# CANBUS_3V3_Isolated.net
KiCad netlist of a schematic drawn in Altium Designer
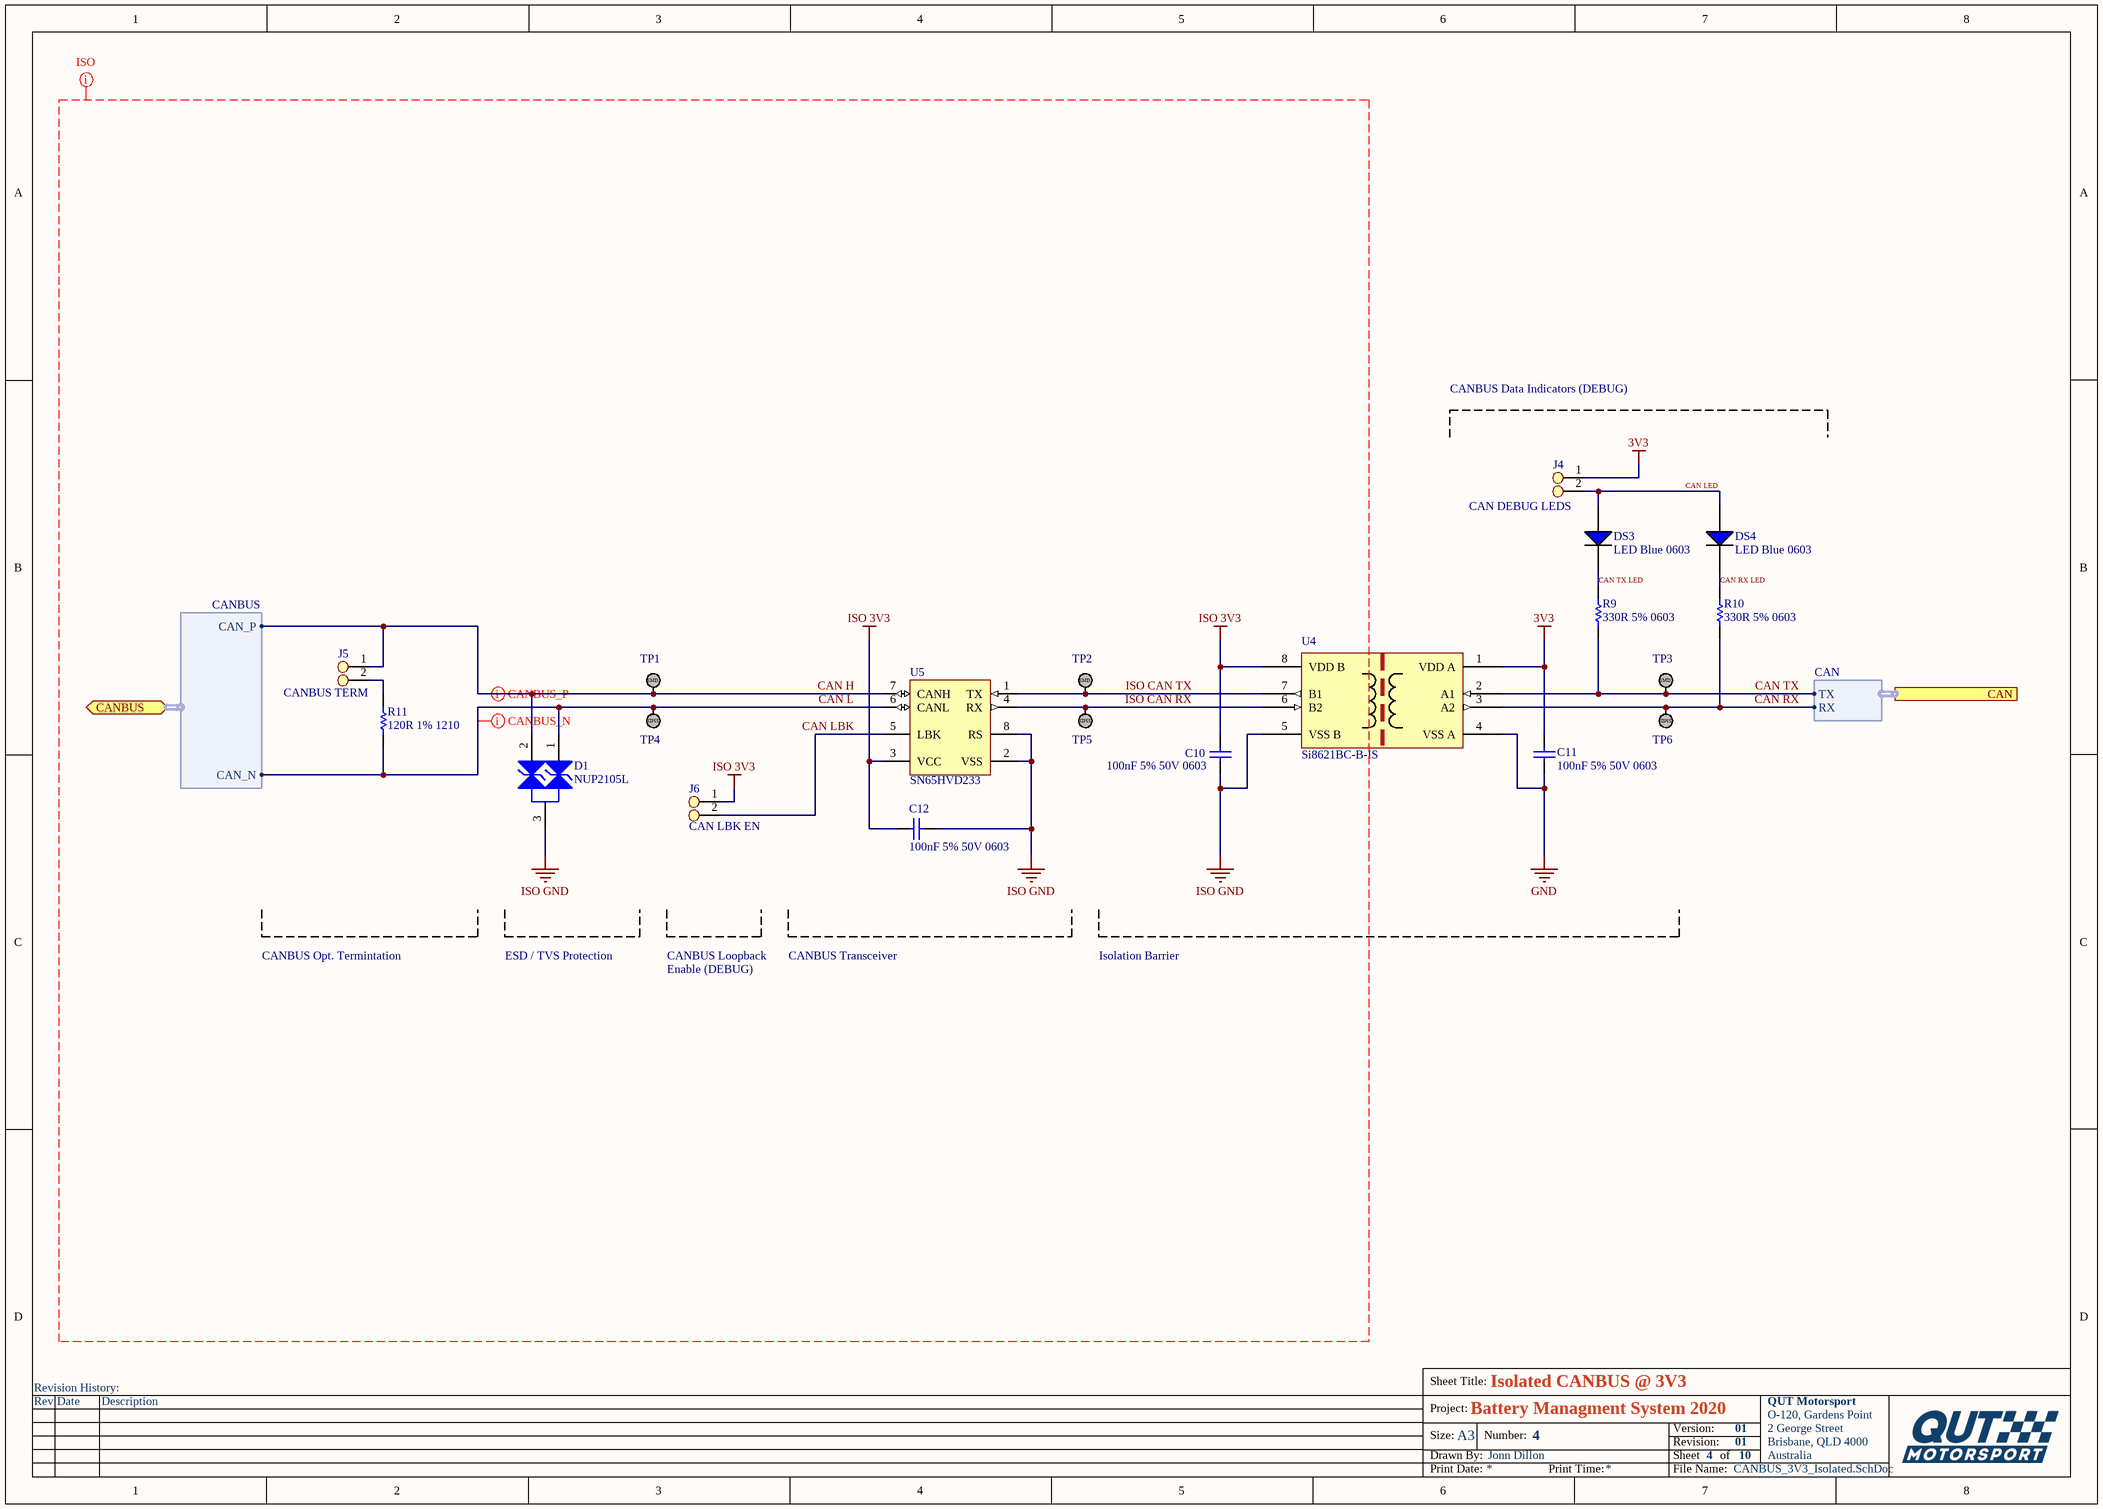
[diagram p0: CANBUS_3V3_Isolated.SchDoc]

(export (version "E")
  (design (tool "Eeschema 10.0.6"))
  (components
    (comp (ref "C10")
      (value "100nF 5% 50V 0603")
      (footprint "CAPC1608X90X35NL15T15")
      (fields
        (field (name "MANUFACTURER") "AVX Interconnect / Elco")
        (field (name "PART NUMBER") "06035C104JAT2A")
      )
      (libsource (lib "Altium Content Vault") (part "CAP"))
    )
    (comp (ref "C11")
      (value "100nF 5% 50V 0603")
      (footprint "CAPC1608X90X35NL15T15")
      (fields
        (field (name "MANUFACTURER") "AVX Interconnect / Elco")
        (field (name "PART NUMBER") "06035C104JAT2A")
      )
      (libsource (lib "Altium Content Vault") (part "CAP"))
    )
    (comp (ref "C12")
      (value "100nF 5% 50V 0603")
      (footprint "CAPC1608X90X35NL15T15")
      (fields
        (field (name "MANUFACTURER") "AVX Interconnect / Elco")
        (field (name "PART NUMBER") "06035C104JAT2A")
      )
      (libsource (lib "Altium Content Vault") (part "CAP"))
    )
    (comp (ref "D1")
      (value "NUP2105L")
      (footprint "NUP2105L")
      (libsource (lib "QUTMS_CANLibrary") (part "NUP2105L"))
    )
    (comp (ref "DS3")
      (value "LED Blue 0603")
      (footprint "LED BLUE 0603")
      (libsource (lib "QUTMS_LEDLibrary") (part "LED BLUE 0603"))
    )
    (comp (ref "DS4")
      (value "LED Blue 0603")
      (footprint "LED BLUE 0603")
      (libsource (lib "QUTMS_LEDLibrary") (part "LED BLUE 0603"))
    )
    (comp (ref "J4")
      (value "CAN DEBUG LEDS")
      (footprint "Jumper_2Way_Pin")
      (description "Jumper_2Way_Pins")
      (libsource (lib "QUTMS_JumperLibrary") (part "Jumper_2Way_Side_Pins"))
    )
    (comp (ref "J5")
      (value "CANBUS TERM")
      (footprint "Jumper_2Way_Pin")
      (description "Jumper_2Way_Pins")
      (libsource (lib "QUTMS_JumperLibrary") (part "Jumper_2Way_Side_Pins"))
    )
    (comp (ref "J6")
      (value "CAN LBK EN")
      (footprint "Jumper_2Way_Pin")
      (description "Jumper_2Way_Pins")
      (libsource (lib "QUTMS_JumperLibrary") (part "Jumper_2Way_Side_Pins"))
    )
    (comp (ref "R9")
      (value "330R 5% 0603")
      (footprint "RESC1608X55X25LL10T15")
      (fields (field (name "MANUFACTURER") "Yageo"))
      (libsource (lib "Altium Content Vault") (part "RES-2"))
    )
    (comp (ref "R10")
      (value "330R 5% 0603")
      (footprint "RESC1608X55X25LL10T15")
      (fields (field (name "MANUFACTURER") "Yageo"))
      (libsource (lib "Altium Content Vault") (part "RES-2"))
    )
    (comp (ref "R11")
      (value "120R 1% 1210")
      (footprint "RESC1210(3225)_M")
      (description "120R 0.5W 1% 1210 (3225 Metric)  SMD")
      (fields (field (name "TOLERANCE") "1 %") (field (name "POWER") "0.5 W"))
      (libsource (lib "Altium Content Vault") (part "RES"))
    )
    (comp (ref "TP1")
      (value "TestPoint_SMD")
      (footprint "TestPointSMD")
      (libsource (lib "StandardTest") (part "TestPoint_SMD"))
    )
    (comp (ref "TP2")
      (value "TestPoint_SMD")
      (footprint "TestPointSMD")
      (libsource (lib "StandardTest") (part "TestPoint_SMD"))
    )
    (comp (ref "TP3")
      (value "TestPoint_SMD")
      (footprint "TestPointSMD")
      (libsource (lib "StandardTest") (part "TestPoint_SMD"))
    )
    (comp (ref "TP4")
      (value "TestPoint_SMD")
      (footprint "TestPointSMD")
      (libsource (lib "StandardTest") (part "TestPoint_SMD"))
    )
    (comp (ref "TP5")
      (value "TestPoint_SMD")
      (footprint "TestPointSMD")
      (libsource (lib "StandardTest") (part "TestPoint_SMD"))
    )
    (comp (ref "TP6")
      (value "TestPoint_SMD")
      (footprint "TestPointSMD")
      (libsource (lib "StandardTest") (part "TestPoint_SMD"))
    )
    (comp (ref "U4") (value "Si8621BC-B-IS") (libsource (lib "QUTMS_IsolatorLibrary") (part "Si8621BC-B-IS")))
    (comp (ref "U5")
      (value "SN65HVD233")
      (footprint "SN65HVD233DR")
      (libsource (lib "QUTMS_CANLibrary") (part "SN65HVD233"))
    )
  )
  (nets
    (net (code "3") (name "/CAN H") (class "Default")
      (node (ref "D1") (pin "2") (pinfunction "2_2") (pintype "passive"))
      (node (ref "J5") (pin "1") (pinfunction "1_1") (pintype "passive"))
      (node (ref "TP1") (pin "1") (pinfunction "1_1") (pintype "passive"))
      (node (ref "U5") (pin "7") (pinfunction "CANH_7") (pintype "bidirectional"))
    )
    (net (code "4") (name "/CAN L") (class "Default")
      (node (ref "D1") (pin "1") (pinfunction "1_1") (pintype "passive"))
      (node (ref "R11") (pin "1") (pinfunction "1_1") (pintype "passive"))
      (node (ref "TP4") (pin "1") (pinfunction "1_1") (pintype "passive"))
      (node (ref "U5") (pin "6") (pinfunction "CANL_6") (pintype "bidirectional"))
    )
    (net (code "5") (name "/CAN LBK") (class "Default")
      (node (ref "J6") (pin "2") (pinfunction "2_2") (pintype "passive"))
      (node (ref "U5") (pin "5") (pinfunction "LBK_5") (pintype "passive"))
    )
    (net (code "6") (name "/CAN LED") (class "Default")
      (node (ref "DS3") (pin "1") (pinfunction "A_1") (pintype "passive"))
      (node (ref "DS4") (pin "1") (pinfunction "A_1") (pintype "passive"))
      (node (ref "J4") (pin "2") (pinfunction "2_2") (pintype "passive"))
    )
    (net (code "7") (name "/CAN RX") (class "Default")
      (node (ref "R10") (pin "1") (pinfunction "1_1") (pintype "passive"))
      (node (ref "TP6") (pin "1") (pinfunction "1_1") (pintype "passive"))
      (node (ref "U4") (pin "3") (pinfunction "A2_3") (pintype "output"))
    )
    (net (code "8") (name "/CAN RX LED") (class "Default")
      (node (ref "DS4") (pin "2") (pinfunction "C_2") (pintype "passive"))
      (node (ref "R10") (pin "2") (pinfunction "2_2") (pintype "passive"))
    )
    (net (code "9") (name "/CAN TX") (class "Default")
      (node (ref "R9") (pin "1") (pinfunction "1_1") (pintype "passive"))
      (node (ref "TP3") (pin "1") (pinfunction "1_1") (pintype "passive"))
      (node (ref "U4") (pin "2") (pinfunction "A1_2") (pintype "input"))
    )
    (net (code "10") (name "/CAN TX LED") (class "Default")
      (node (ref "DS3") (pin "2") (pinfunction "C_2") (pintype "passive"))
      (node (ref "R9") (pin "2") (pinfunction "2_2") (pintype "passive"))
    )
    (net (code "11") (name "/ISO CAN RX") (class "Default")
      (node (ref "TP5") (pin "1") (pinfunction "1_1") (pintype "passive"))
      (node (ref "U4") (pin "6") (pinfunction "B2_6") (pintype "input"))
      (node (ref "U5") (pin "4") (pinfunction "RX_4") (pintype "output"))
    )
    (net (code "12") (name "/ISO CAN TX") (class "Default")
      (node (ref "TP2") (pin "1") (pinfunction "1_1") (pintype "passive"))
      (node (ref "U4") (pin "7") (pinfunction "B1_7") (pintype "output"))
      (node (ref "U5") (pin "1") (pinfunction "TX_1") (pintype "input"))
    )
    (net (code "15") (name "3V3") (class "Default")
      (node (ref "C11") (pin "1") (pinfunction "1_1") (pintype "passive"))
      (node (ref "J4") (pin "1") (pinfunction "1_1") (pintype "passive"))
      (node (ref "U4") (pin "1") (pinfunction "VDD_A_1") (pintype "passive"))
    )
    (net (code "16") (name "GND") (class "Default")
      (node (ref "C11") (pin "2") (pinfunction "2_2") (pintype "passive"))
      (node (ref "U4") (pin "4") (pinfunction "VSS_A_4") (pintype "passive"))
    )
    (net (code "17") (name "ISO 3V3") (class "Default")
      (node (ref "C10") (pin "1") (pinfunction "1_1") (pintype "passive"))
      (node (ref "C12") (pin "1") (pinfunction "1_1") (pintype "passive"))
      (node (ref "J6") (pin "1") (pinfunction "1_1") (pintype "passive"))
      (node (ref "U4") (pin "8") (pinfunction "VDD_B_8") (pintype "passive"))
      (node (ref "U5") (pin "3") (pinfunction "VCC_3") (pintype "passive"))
    )
    (net (code "18") (name "ISO GND") (class "Default")
      (node (ref "C10") (pin "2") (pinfunction "2_2") (pintype "passive"))
      (node (ref "C12") (pin "2") (pinfunction "2_2") (pintype "passive"))
      (node (ref "D1") (pin "3") (pinfunction "3_3") (pintype "passive"))
      (node (ref "U4") (pin "5") (pinfunction "VSS_B_5") (pintype "passive"))
      (node (ref "U5") (pin "2") (pinfunction "VSS_2") (pintype "passive"))
      (node (ref "U5") (pin "8") (pinfunction "RS_8") (pintype "passive"))
    )
    (net (code "19") (name "Net-(J5-Pad2)") (class "Default")
      (node (ref "J5") (pin "2") (pinfunction "2_2") (pintype "passive"))
      (node (ref "R11") (pin "2") (pinfunction "2_2") (pintype "passive"))
    )
  )
)
